# 5ObstacleNAND.net
KiCad netlist of a schematic drawn in EAGLE
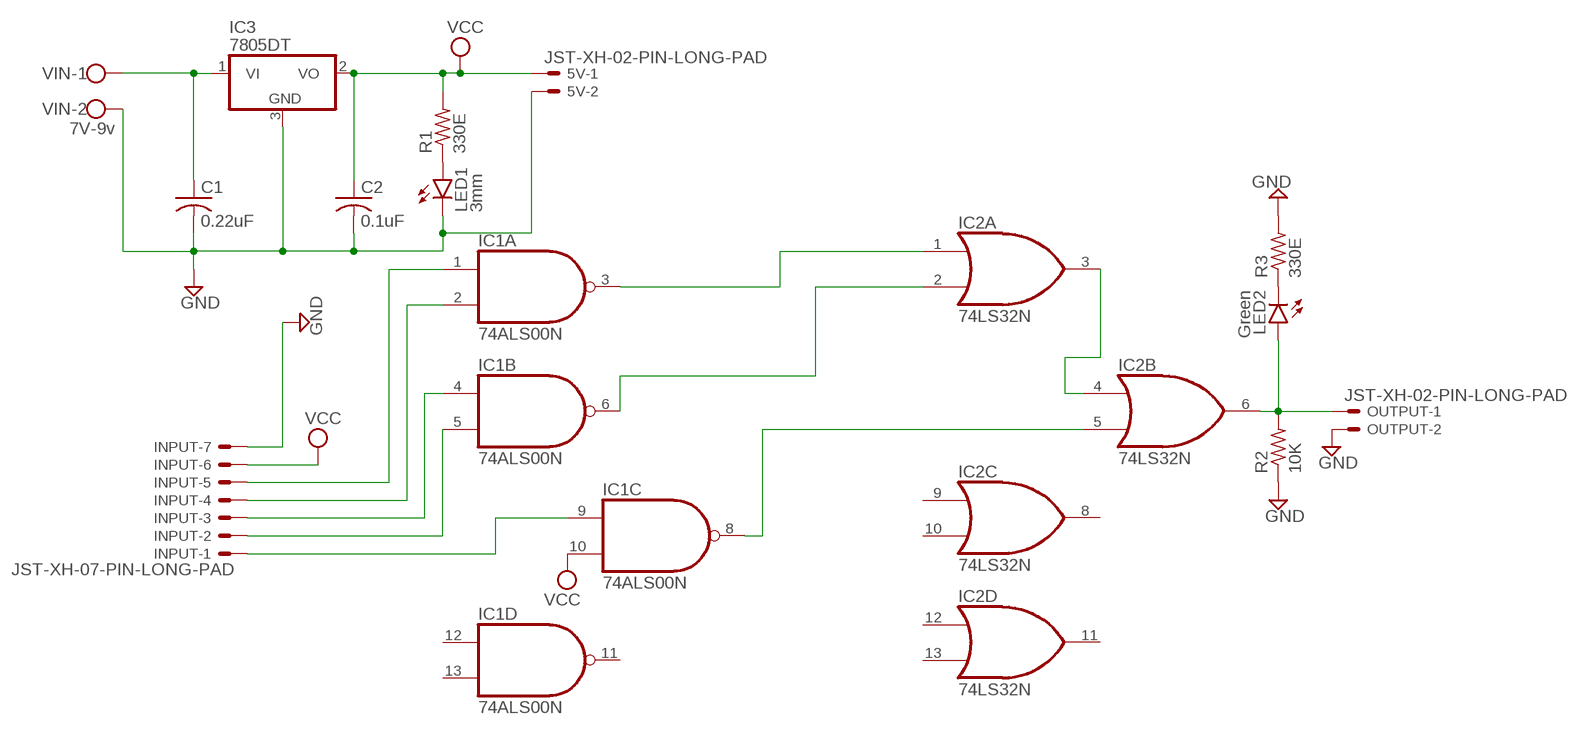
[diagram p0: schematic, sheet 1]

(export (version "E")
  (design (tool "Eeschema 10.0.6"))
  (components
    (comp (ref "5V")
      (value "JST-XH-02-PIN-LONG-PAD")
      (footprint "eagle-import:JST-XH-02-PACKAGE-LONG-PAD")
      (libsource (lib "eagle-import") (part "JST-XH-02-PIN-LONG-PAD"))
    )
    (comp (ref "C1")
      (value "0.22uF")
      (footprint "eagle-import:C0805")
      (libsource (lib "eagle-import") (part "C-USC0805"))
    )
    (comp (ref "C2")
      (value "0.1uF")
      (footprint "eagle-import:C0805")
      (libsource (lib "eagle-import") (part "C-USC0805"))
    )
    (comp (ref "IC1")
      (value "74ALS00N")
      (footprint "eagle-import:DIL14")
      (libsource (lib "eagle-import") (part "7400NALS"))
    )
    (comp (ref "IC2")
      (value "74LS32N")
      (footprint "eagle-import:DIL14")
      (libsource (lib "eagle-import") (part "7432NLS"))
    )
    (comp (ref "IC3")
      (value "7805DT")
      (footprint "eagle-import:TO252")
      (libsource (lib "eagle-import") (part "78DT05"))
    )
    (comp (ref "INPUT")
      (value "JST-XH-07-PIN-LONG-PAD")
      (footprint "eagle-import:JST-XH-07-PACKAGE-LONG-PAD")
      (libsource (lib "eagle-import") (part "JST-XH-07-PIN-LONG-PAD"))
    )
    (comp (ref "LED1")
      (value "3mm")
      (footprint "eagle-import:SML0805")
      (libsource (lib "eagle-import") (part "LEDSML0805"))
    )
    (comp (ref "LED2")
      (value "Green")
      (footprint "eagle-import:SML0805")
      (libsource (lib "eagle-import") (part "LEDSML0805"))
    )
    (comp (ref "OUTPUT")
      (value "JST-XH-02-PIN-LONG-PAD")
      (footprint "eagle-import:JST-XH-02-PACKAGE-LONG-PAD")
      (libsource (lib "eagle-import") (part "JST-XH-02-PIN-LONG-PAD"))
    )
    (comp (ref "R1")
      (value "330E")
      (footprint "eagle-import:R0805")
      (libsource (lib "eagle-import") (part "R-US_R0805"))
    )
    (comp (ref "R2")
      (value "10K")
      (footprint "eagle-import:R0805")
      (libsource (lib "eagle-import") (part "R-US_R0805"))
    )
    (comp (ref "R3")
      (value "330E")
      (footprint "eagle-import:R0805")
      (libsource (lib "eagle-import") (part "R-US_R0805"))
    )
    (comp (ref "VIN")
      (value "7V-9v")
      (footprint "eagle-import:W237-102")
      (fields (field (name "MPN") "237-102"))
      (libsource (lib "eagle-import") (part "W237-102"))
    )
  )
  (nets
    (net (code "1") (name "GND") (class "Default")
      (node (ref "5V") (pin "2") (pinfunction "S_2") (pintype "passive"))
      (node (ref "C1") (pin "2") (pinfunction "2_2") (pintype "passive"))
      (node (ref "C2") (pin "2") (pinfunction "2_2") (pintype "passive"))
      (node (ref "IC3") (pin "3") (pinfunction "GND_3") (pintype "passive"))
      (node (ref "INPUT") (pin "7") (pinfunction "S_7") (pintype "passive"))
      (node (ref "LED1") (pin "C") (pinfunction "C_C") (pintype "passive"))
      (node (ref "OUTPUT") (pin "2") (pinfunction "S_2") (pintype "passive"))
      (node (ref "R2") (pin "1") (pinfunction "1_1") (pintype "passive"))
      (node (ref "R3") (pin "2") (pinfunction "2_2") (pintype "passive"))
      (node (ref "VIN") (pin "2") (pinfunction "KL_2") (pintype "passive"))
    )
    (net (code "2") (name "Net-(IC1A-I0)") (class "Default")
      (node (ref "IC1") (pin "1") (pinfunction "I0_1") (pintype "input"))
      (node (ref "INPUT") (pin "5") (pinfunction "S_5") (pintype "passive"))
    )
    (net (code "3") (name "Net-(IC1A-I1)") (class "Default")
      (node (ref "IC1") (pin "2") (pinfunction "I1_2") (pintype "input"))
      (node (ref "INPUT") (pin "4") (pinfunction "S_4") (pintype "passive"))
    )
    (net (code "4") (name "Net-(IC1A-O)") (class "Default")
      (node (ref "IC1") (pin "3") (pinfunction "O_3") (pintype "output"))
      (node (ref "IC2") (pin "1") (pinfunction "I0_1") (pintype "input"))
    )
    (net (code "5") (name "Net-(IC1B-I0)") (class "Default")
      (node (ref "IC1") (pin "4") (pinfunction "I0_4") (pintype "input"))
      (node (ref "INPUT") (pin "3") (pinfunction "S_3") (pintype "passive"))
    )
    (net (code "6") (name "Net-(IC1B-I1)") (class "Default")
      (node (ref "IC1") (pin "5") (pinfunction "I1_5") (pintype "input"))
      (node (ref "INPUT") (pin "2") (pinfunction "S_2") (pintype "passive"))
    )
    (net (code "7") (name "Net-(IC1B-O)") (class "Default")
      (node (ref "IC1") (pin "6") (pinfunction "O_6") (pintype "output"))
      (node (ref "IC2") (pin "2") (pinfunction "I1_2") (pintype "input"))
    )
    (net (code "8") (name "Net-(IC1C-I0)") (class "Default")
      (node (ref "IC1") (pin "9") (pinfunction "I0_9") (pintype "input"))
      (node (ref "INPUT") (pin "1") (pinfunction "S_1") (pintype "passive"))
    )
    (net (code "9") (name "Net-(IC1C-O)") (class "Default")
      (node (ref "IC1") (pin "8") (pinfunction "O_8") (pintype "output"))
      (node (ref "IC2") (pin "5") (pinfunction "I1_5") (pintype "input"))
    )
    (net (code "10") (name "Net-(IC2A-O)") (class "Default")
      (node (ref "IC2") (pin "3") (pinfunction "O_3") (pintype "output"))
      (node (ref "IC2") (pin "4") (pinfunction "I0_4") (pintype "input"))
    )
    (net (code "11") (name "Net-(IC2B-O)") (class "Default")
      (node (ref "IC2") (pin "6") (pinfunction "O_6") (pintype "output"))
      (node (ref "LED2") (pin "A") (pinfunction "A_A") (pintype "passive"))
      (node (ref "OUTPUT") (pin "1") (pinfunction "S_1") (pintype "passive"))
      (node (ref "R2") (pin "2") (pinfunction "2_2") (pintype "passive"))
    )
    (net (code "12") (name "Net-(IC3-VI)") (class "Default")
      (node (ref "C1") (pin "1") (pinfunction "1_1") (pintype "passive"))
      (node (ref "IC3") (pin "1") (pinfunction "VI_1") (pintype "input"))
      (node (ref "VIN") (pin "1") (pinfunction "KL_1") (pintype "passive"))
    )
    (net (code "13") (name "Net-(LED1-PadA)") (class "Default")
      (node (ref "LED1") (pin "A") (pinfunction "A_A") (pintype "passive"))
      (node (ref "R1") (pin "1") (pinfunction "1_1") (pintype "passive"))
    )
    (net (code "14") (name "Net-(LED2-PadC)") (class "Default")
      (node (ref "LED2") (pin "C") (pinfunction "C_C") (pintype "passive"))
      (node (ref "R3") (pin "1") (pinfunction "1_1") (pintype "passive"))
    )
    (net (code "15") (name "VCC") (class "Default")
      (node (ref "5V") (pin "1") (pinfunction "S_1") (pintype "passive"))
      (node (ref "C2") (pin "1") (pinfunction "1_1") (pintype "passive"))
      (node (ref "IC1") (pin "10") (pinfunction "I1_10") (pintype "input"))
      (node (ref "IC3") (pin "2") (pinfunction "VO_2") (pintype "passive"))
      (node (ref "INPUT") (pin "6") (pinfunction "S_6") (pintype "passive"))
      (node (ref "R1") (pin "2") (pinfunction "2_2") (pintype "passive"))
    )
    (net (code "16") (name "unconnected-(IC1D-I0-Pad12)") (class "Default")
      (node (ref "IC1") (pin "12") (pinfunction "I0_12") (pintype "input"))
    )
    (net (code "17") (name "unconnected-(IC1D-I1-Pad13)") (class "Default")
      (node (ref "IC1") (pin "13") (pinfunction "I1_13") (pintype "input"))
    )
    (net (code "18") (name "unconnected-(IC1D-O-Pad11)") (class "Default")
      (node (ref "IC1") (pin "11") (pinfunction "O_11") (pintype "output"))
    )
    (net (code "19") (name "unconnected-(IC2C-I0-Pad9)") (class "Default")
      (node (ref "IC2") (pin "9") (pinfunction "I0_9") (pintype "input"))
    )
    (net (code "20") (name "unconnected-(IC2C-I1-Pad10)") (class "Default")
      (node (ref "IC2") (pin "10") (pinfunction "I1_10") (pintype "input"))
    )
    (net (code "21") (name "unconnected-(IC2C-O-Pad8)") (class "Default")
      (node (ref "IC2") (pin "8") (pinfunction "O_8") (pintype "output"))
    )
    (net (code "22") (name "unconnected-(IC2D-I0-Pad12)") (class "Default")
      (node (ref "IC2") (pin "12") (pinfunction "I0_12") (pintype "input"))
    )
    (net (code "23") (name "unconnected-(IC2D-I1-Pad13)") (class "Default")
      (node (ref "IC2") (pin "13") (pinfunction "I1_13") (pintype "input"))
    )
    (net (code "24") (name "unconnected-(IC2D-O-Pad11)") (class "Default")
      (node (ref "IC2") (pin "11") (pinfunction "O_11") (pintype "output"))
    )
  )
)
